# 10_HDMI.net
KiCad netlist of a schematic drawn in Altium Designer
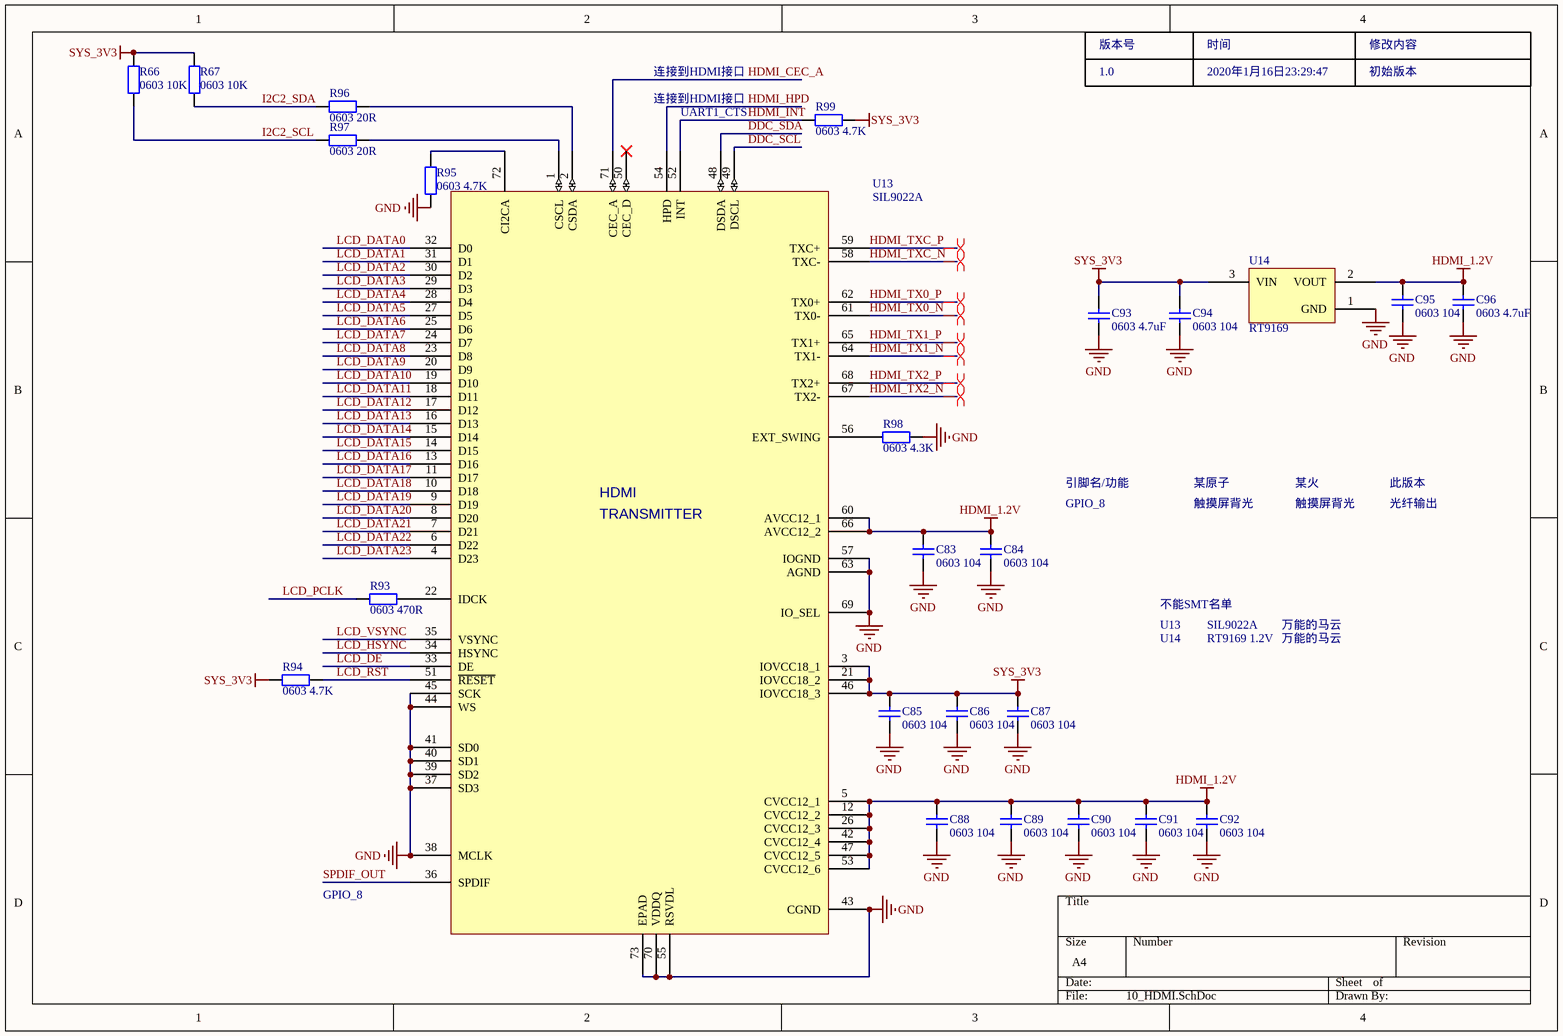
[diagram p0: 10_HDMI.SchDoc]

(export (version "E")
  (design (tool "Eeschema 10.0.6"))
  (components
    (comp (ref "C83")
      (value "0603 104")
      (footprint "LC-0603_C")
      (description "贴片电容")
      (libsource (lib "JLC") (part "0603 1.5nF (152) 10% 50V"))
    )
    (comp (ref "C84")
      (value "0603 104")
      (footprint "LC-0603_C")
      (description "贴片电容")
      (libsource (lib "JLC") (part "0603 1.5nF (152) 10% 50V"))
    )
    (comp (ref "C85")
      (value "0603 104")
      (footprint "LC-0603_C")
      (description "贴片电容")
      (libsource (lib "JLC") (part "0603 1.5nF (152) 10% 50V"))
    )
    (comp (ref "C86")
      (value "0603 104")
      (footprint "LC-0603_C")
      (description "贴片电容")
      (libsource (lib "JLC") (part "0603 1.5nF (152) 10% 50V"))
    )
    (comp (ref "C87")
      (value "0603 104")
      (footprint "LC-0603_C")
      (description "贴片电容")
      (libsource (lib "JLC") (part "0603 1.5nF (152) 10% 50V"))
    )
    (comp (ref "C88")
      (value "0603 104")
      (footprint "LC-0603_C")
      (description "贴片电容")
      (libsource (lib "JLC") (part "0603 1.5nF (152) 10% 50V"))
    )
    (comp (ref "C89")
      (value "0603 104")
      (footprint "LC-0603_C")
      (description "贴片电容")
      (libsource (lib "JLC") (part "0603 1.5nF (152) 10% 50V"))
    )
    (comp (ref "C90")
      (value "0603 104")
      (footprint "LC-0603_C")
      (description "贴片电容")
      (libsource (lib "JLC") (part "0603 1.5nF (152) 10% 50V"))
    )
    (comp (ref "C91")
      (value "0603 104")
      (footprint "LC-0603_C")
      (description "贴片电容")
      (libsource (lib "JLC") (part "0603 1.5nF (152) 10% 50V"))
    )
    (comp (ref "C92")
      (value "0603 104")
      (footprint "LC-0603_C")
      (description "贴片电容")
      (libsource (lib "JLC") (part "0603 1.5nF (152) 10% 50V"))
    )
    (comp (ref "C93")
      (value "0603 4.7uF")
      (footprint "LC-0603_C")
      (description "贴片电容")
      (libsource (lib "JLC") (part "0603 1.5nF (152) 10% 50V"))
    )
    (comp (ref "C94")
      (value "0603 104")
      (footprint "LC-0603_C")
      (description "贴片电容")
      (libsource (lib "JLC") (part "0603 1.5nF (152) 10% 50V"))
    )
    (comp (ref "C95")
      (value "0603 104")
      (footprint "LC-0603_C")
      (description "贴片电容")
      (libsource (lib "JLC") (part "0603 1.5nF (152) 10% 50V"))
    )
    (comp (ref "C96")
      (value "0603 4.7uF")
      (footprint "LC-0603_C")
      (description "贴片电容")
      (libsource (lib "JLC") (part "0603 1.5nF (152) 10% 50V"))
    )
    (comp (ref "R66")
      (value "0603 10K")
      (footprint "LC-0603_R")
      (description "贴片电阻")
      (libsource (lib "") (part "0603 1.1KΩ (1101) 1%_1"))
    )
    (comp (ref "R67")
      (value "0603 10K")
      (footprint "LC-0603_R")
      (description "贴片电阻")
      (libsource (lib "") (part "0603 1.1KΩ (1101) 1%_1"))
    )
    (comp (ref "R93")
      (value "0603 470R")
      (footprint "LC-0603_R")
      (description "贴片电阻")
      (libsource (lib "") (part "0603 1.1KΩ (1101) 1%_2"))
    )
    (comp (ref "R94")
      (value "0603 4.7K")
      (footprint "LC-0603_R")
      (description "贴片电阻")
      (libsource (lib "") (part "0603 1.1KΩ (1101) 1%_2"))
    )
    (comp (ref "R95")
      (value "0603 4.7K")
      (footprint "LC-0603_R")
      (description "贴片电阻")
      (libsource (lib "") (part "0603 1.1KΩ (1101) 1%_3"))
    )
    (comp (ref "R96")
      (value "0603 20R")
      (footprint "LC-0603_R")
      (description "贴片电阻")
      (libsource (lib "JLC") (part "0603 1.1KΩ (1101) 1%"))
    )
    (comp (ref "R97")
      (value "0603 20R")
      (footprint "LC-0603_R")
      (description "贴片电阻")
      (libsource (lib "JLC") (part "0603 1.1KΩ (1101) 1%"))
    )
    (comp (ref "R98")
      (value "0603 4.3K")
      (footprint "LC-0603_R")
      (description "贴片电阻")
      (libsource (lib "JLC") (part "0603 1.1KΩ (1101) 1%"))
    )
    (comp (ref "R99")
      (value "0603 4.7K")
      (footprint "LC-0603_R")
      (description "贴片电阻")
      (libsource (lib "JLC") (part "0603 1.1KΩ (1101) 1%"))
    )
    (comp (ref "U13")
      (value "SIL9022A")
      (footprint "QFN72_10X10")
      (libsource (lib "Integrated_Library2") (part "SIL9022A"))
    )
    (comp (ref "U14")
      (value "RT9169")
      (footprint "LC-SOT-23(SOT-23-3)")
      (libsource (lib "Integrated_Library2") (part "RT9169"))
    )
  )
  (nets
    (net (code "1") (name "/DDC_SCL") (class "Default")
      (node (ref "U13") (pin "49") (pinfunction "DSCL_49") (pintype "bidirectional"))
    )
    (net (code "2") (name "/DDC_SDA") (class "Default")
      (node (ref "U13") (pin "48") (pinfunction "DSDA_48") (pintype "bidirectional"))
    )
    (net (code "3") (name "/HDMI_CEC_A") (class "Default")
      (node (ref "U13") (pin "71") (pinfunction "CEC_A_71") (pintype "bidirectional"))
    )
    (net (code "4") (name "/HDMI_HPD") (class "Default")
      (node (ref "U13") (pin "54") (pinfunction "HPD_54") (pintype "passive"))
    )
    (net (code "5") (name "/HDMI_INT") (class "Default")
      (node (ref "R99") (pin "1") (pinfunction "1_1") (pintype "passive"))
      (node (ref "U13") (pin "52") (pinfunction "INT_52") (pintype "passive"))
    )
    (net (code "6") (name "/HDMI_TX0_N") (class "Default")
      (node (ref "U13") (pin "61") (pinfunction "TX0-_61") (pintype "passive"))
    )
    (net (code "7") (name "/HDMI_TX0_P") (class "Default")
      (node (ref "U13") (pin "62") (pinfunction "TX0+_62") (pintype "passive"))
    )
    (net (code "8") (name "/HDMI_TX1_N") (class "Default")
      (node (ref "U13") (pin "64") (pinfunction "TX1-_64") (pintype "passive"))
    )
    (net (code "9") (name "/HDMI_TX1_P") (class "Default")
      (node (ref "U13") (pin "65") (pinfunction "TX1+_65") (pintype "passive"))
    )
    (net (code "10") (name "/HDMI_TX2_N") (class "Default")
      (node (ref "U13") (pin "67") (pinfunction "TX2-_67") (pintype "passive"))
    )
    (net (code "11") (name "/HDMI_TX2_P") (class "Default")
      (node (ref "U13") (pin "68") (pinfunction "TX2+_68") (pintype "passive"))
    )
    (net (code "12") (name "/HDMI_TXC_N") (class "Default")
      (node (ref "U13") (pin "58") (pinfunction "TXC-_58") (pintype "passive"))
    )
    (net (code "13") (name "/HDMI_TXC_P") (class "Default")
      (node (ref "U13") (pin "59") (pinfunction "TXC+_59") (pintype "passive"))
    )
    (net (code "14") (name "/I2C2_SCL") (class "Default")
      (node (ref "R66") (pin "1") (pinfunction "1_1") (pintype "passive"))
      (node (ref "R97") (pin "1") (pinfunction "1_1") (pintype "passive"))
    )
    (net (code "15") (name "/I2C2_SDA") (class "Default")
      (node (ref "R67") (pin "1") (pinfunction "1_1") (pintype "passive"))
      (node (ref "R96") (pin "1") (pinfunction "1_1") (pintype "passive"))
    )
    (net (code "16") (name "/LCD_DATA0") (class "Default")
      (node (ref "U13") (pin "32") (pinfunction "D0_32") (pintype "passive"))
    )
    (net (code "17") (name "/LCD_DATA1") (class "Default")
      (node (ref "U13") (pin "31") (pinfunction "D1_31") (pintype "passive"))
    )
    (net (code "18") (name "/LCD_DATA2") (class "Default")
      (node (ref "U13") (pin "30") (pinfunction "D2_30") (pintype "passive"))
    )
    (net (code "19") (name "/LCD_DATA3") (class "Default")
      (node (ref "U13") (pin "29") (pinfunction "D3_29") (pintype "passive"))
    )
    (net (code "20") (name "/LCD_DATA4") (class "Default")
      (node (ref "U13") (pin "28") (pinfunction "D4_28") (pintype "passive"))
    )
    (net (code "21") (name "/LCD_DATA5") (class "Default")
      (node (ref "U13") (pin "27") (pinfunction "D5_27") (pintype "passive"))
    )
    (net (code "22") (name "/LCD_DATA6") (class "Default")
      (node (ref "U13") (pin "25") (pinfunction "D6_25") (pintype "passive"))
    )
    (net (code "23") (name "/LCD_DATA7") (class "Default")
      (node (ref "U13") (pin "24") (pinfunction "D7_24") (pintype "passive"))
    )
    (net (code "24") (name "/LCD_DATA8") (class "Default")
      (node (ref "U13") (pin "23") (pinfunction "D8_23") (pintype "passive"))
    )
    (net (code "25") (name "/LCD_DATA9") (class "Default")
      (node (ref "U13") (pin "20") (pinfunction "D9_20") (pintype "passive"))
    )
    (net (code "26") (name "/LCD_DATA10") (class "Default")
      (node (ref "U13") (pin "19") (pinfunction "D10_19") (pintype "passive"))
    )
    (net (code "27") (name "/LCD_DATA11") (class "Default")
      (node (ref "U13") (pin "18") (pinfunction "D11_18") (pintype "passive"))
    )
    (net (code "28") (name "/LCD_DATA12") (class "Default")
      (node (ref "U13") (pin "17") (pinfunction "D12_17") (pintype "passive"))
    )
    (net (code "29") (name "/LCD_DATA13") (class "Default")
      (node (ref "U13") (pin "16") (pinfunction "D13_16") (pintype "passive"))
    )
    (net (code "30") (name "/LCD_DATA14") (class "Default")
      (node (ref "U13") (pin "15") (pinfunction "D14_15") (pintype "passive"))
    )
    (net (code "31") (name "/LCD_DATA15") (class "Default")
      (node (ref "U13") (pin "14") (pinfunction "D15_14") (pintype "passive"))
    )
    (net (code "32") (name "/LCD_DATA16") (class "Default")
      (node (ref "U13") (pin "13") (pinfunction "D16_13") (pintype "passive"))
    )
    (net (code "33") (name "/LCD_DATA17") (class "Default")
      (node (ref "U13") (pin "11") (pinfunction "D17_11") (pintype "passive"))
    )
    (net (code "34") (name "/LCD_DATA18") (class "Default")
      (node (ref "U13") (pin "10") (pinfunction "D18_10") (pintype "passive"))
    )
    (net (code "35") (name "/LCD_DATA19") (class "Default")
      (node (ref "U13") (pin "9") (pinfunction "D19_9") (pintype "passive"))
    )
    (net (code "36") (name "/LCD_DATA20") (class "Default")
      (node (ref "U13") (pin "8") (pinfunction "D20_8") (pintype "passive"))
    )
    (net (code "37") (name "/LCD_DATA21") (class "Default")
      (node (ref "U13") (pin "7") (pinfunction "D21_7") (pintype "passive"))
    )
    (net (code "38") (name "/LCD_DATA22") (class "Default")
      (node (ref "U13") (pin "6") (pinfunction "D22_6") (pintype "passive"))
    )
    (net (code "39") (name "/LCD_DATA23") (class "Default")
      (node (ref "U13") (pin "4") (pinfunction "D23_4") (pintype "passive"))
    )
    (net (code "40") (name "/LCD_DE") (class "Default")
      (node (ref "U13") (pin "33") (pinfunction "DE_33") (pintype "passive"))
    )
    (net (code "41") (name "/LCD_HSYNC") (class "Default")
      (node (ref "U13") (pin "34") (pinfunction "HSYNC_34") (pintype "passive"))
    )
    (net (code "42") (name "/LCD_PCLK") (class "Default")
      (node (ref "R93") (pin "2") (pinfunction "2_2") (pintype "passive"))
    )
    (net (code "43") (name "/LCD_RST") (class "Default")
      (node (ref "R94") (pin "1") (pinfunction "1_1") (pintype "passive"))
      (node (ref "U13") (pin "51") (pinfunction "RESET_51") (pintype "passive"))
    )
    (net (code "44") (name "/LCD_VSYNC") (class "Default")
      (node (ref "U13") (pin "35") (pinfunction "VSYNC_35") (pintype "passive"))
    )
    (net (code "45") (name "/SPDIF_OUT") (class "Default")
      (node (ref "U13") (pin "36") (pinfunction "SPDIF_36") (pintype "passive"))
    )
    (net (code "46") (name "GND") (class "Default")
      (node (ref "C83") (pin "2") (pinfunction "2_2") (pintype "passive"))
      (node (ref "C84") (pin "2") (pinfunction "2_2") (pintype "passive"))
      (node (ref "C85") (pin "2") (pinfunction "2_2") (pintype "passive"))
      (node (ref "C86") (pin "2") (pinfunction "2_2") (pintype "passive"))
      (node (ref "C87") (pin "2") (pinfunction "2_2") (pintype "passive"))
      (node (ref "C88") (pin "2") (pinfunction "2_2") (pintype "passive"))
      (node (ref "C89") (pin "2") (pinfunction "2_2") (pintype "passive"))
      (node (ref "C90") (pin "2") (pinfunction "2_2") (pintype "passive"))
      (node (ref "C91") (pin "2") (pinfunction "2_2") (pintype "passive"))
      (node (ref "C92") (pin "2") (pinfunction "2_2") (pintype "passive"))
      (node (ref "C93") (pin "2") (pinfunction "2_2") (pintype "passive"))
      (node (ref "C94") (pin "2") (pinfunction "2_2") (pintype "passive"))
      (node (ref "C95") (pin "2") (pinfunction "2_2") (pintype "passive"))
      (node (ref "C96") (pin "2") (pinfunction "2_2") (pintype "passive"))
      (node (ref "R95") (pin "2") (pinfunction "2_2") (pintype "passive"))
      (node (ref "R98") (pin "2") (pinfunction "2_2") (pintype "passive"))
      (node (ref "U13") (pin "37") (pinfunction "SD3_37") (pintype "passive"))
      (node (ref "U13") (pin "38") (pinfunction "MCLK_38") (pintype "passive"))
      (node (ref "U13") (pin "39") (pinfunction "SD2_39") (pintype "passive"))
      (node (ref "U13") (pin "40") (pinfunction "SD1_40") (pintype "passive"))
      (node (ref "U13") (pin "41") (pinfunction "SD0_41") (pintype "passive"))
      (node (ref "U13") (pin "43") (pinfunction "CGND_43") (pintype "power_in"))
      (node (ref "U13") (pin "44") (pinfunction "WS_44") (pintype "passive"))
      (node (ref "U13") (pin "45") (pinfunction "SCK_45") (pintype "passive"))
      (node (ref "U13") (pin "55") (pinfunction "RSVDL_55") (pintype "passive"))
      (node (ref "U13") (pin "57") (pinfunction "IOGND_57") (pintype "power_in"))
      (node (ref "U13") (pin "63") (pinfunction "AGND_63") (pintype "power_in"))
      (node (ref "U13") (pin "69") (pinfunction "IO_SEL_69") (pintype "passive"))
      (node (ref "U13") (pin "70") (pinfunction "VDDQ_70") (pintype "power_in"))
      (node (ref "U13") (pin "73") (pinfunction "EPAD_73") (pintype "power_in"))
      (node (ref "U14") (pin "1") (pinfunction "GND_1") (pintype "passive"))
    )
    (net (code "47") (name "HDMI_1.2V") (class "Default")
      (node (ref "C83") (pin "1") (pinfunction "1_1") (pintype "passive"))
      (node (ref "C84") (pin "1") (pinfunction "1_1") (pintype "passive"))
      (node (ref "C88") (pin "1") (pinfunction "1_1") (pintype "passive"))
      (node (ref "C89") (pin "1") (pinfunction "1_1") (pintype "passive"))
      (node (ref "C90") (pin "1") (pinfunction "1_1") (pintype "passive"))
      (node (ref "C91") (pin "1") (pinfunction "1_1") (pintype "passive"))
      (node (ref "C92") (pin "1") (pinfunction "1_1") (pintype "passive"))
      (node (ref "C95") (pin "1") (pinfunction "1_1") (pintype "passive"))
      (node (ref "C96") (pin "1") (pinfunction "1_1") (pintype "passive"))
      (node (ref "U13") (pin "12") (pinfunction "CVCC12_2_12") (pintype "power_in"))
      (node (ref "U13") (pin "26") (pinfunction "CVCC12_3_26") (pintype "power_in"))
      (node (ref "U13") (pin "42") (pinfunction "CVCC12_4_42") (pintype "power_in"))
      (node (ref "U13") (pin "47") (pinfunction "CVCC12_5_47") (pintype "power_in"))
      (node (ref "U13") (pin "5") (pinfunction "CVCC12_1_5") (pintype "power_in"))
      (node (ref "U13") (pin "53") (pinfunction "CVCC12_6_53") (pintype "power_in"))
      (node (ref "U13") (pin "60") (pinfunction "AVCC12_1_60") (pintype "power_in"))
      (node (ref "U13") (pin "66") (pinfunction "AVCC12_2_66") (pintype "power_in"))
      (node (ref "U14") (pin "2") (pinfunction "VOUT_2") (pintype "passive"))
    )
    (net (code "48") (name "Net-(U13-CI2CA)") (class "Default")
      (node (ref "R95") (pin "1") (pinfunction "1_1") (pintype "passive"))
      (node (ref "U13") (pin "72") (pinfunction "CI2CA_72") (pintype "passive"))
    )
    (net (code "49") (name "Net-(U13-CSCL)") (class "Default")
      (node (ref "R97") (pin "2") (pinfunction "2_2") (pintype "passive"))
      (node (ref "U13") (pin "1") (pinfunction "CSCL_1") (pintype "bidirectional"))
    )
    (net (code "50") (name "Net-(U13-CSDA)") (class "Default")
      (node (ref "R96") (pin "2") (pinfunction "2_2") (pintype "passive"))
      (node (ref "U13") (pin "2") (pinfunction "CSDA_2") (pintype "bidirectional"))
    )
    (net (code "51") (name "Net-(U13-EXT_SWING)") (class "Default")
      (node (ref "R98") (pin "1") (pinfunction "1_1") (pintype "passive"))
      (node (ref "U13") (pin "56") (pinfunction "EXT_SWING_56") (pintype "passive"))
    )
    (net (code "52") (name "Net-(U13-IDCK)") (class "Default")
      (node (ref "R93") (pin "1") (pinfunction "1_1") (pintype "passive"))
      (node (ref "U13") (pin "22") (pinfunction "IDCK_22") (pintype "passive"))
    )
    (net (code "53") (name "SYS_3V3") (class "Default")
      (node (ref "C85") (pin "1") (pinfunction "1_1") (pintype "passive"))
      (node (ref "C86") (pin "1") (pinfunction "1_1") (pintype "passive"))
      (node (ref "C87") (pin "1") (pinfunction "1_1") (pintype "passive"))
      (node (ref "C93") (pin "1") (pinfunction "1_1") (pintype "passive"))
      (node (ref "C94") (pin "1") (pinfunction "1_1") (pintype "passive"))
      (node (ref "R66") (pin "2") (pinfunction "2_2") (pintype "passive"))
      (node (ref "R67") (pin "2") (pinfunction "2_2") (pintype "passive"))
      (node (ref "R94") (pin "2") (pinfunction "2_2") (pintype "passive"))
      (node (ref "R99") (pin "2") (pinfunction "2_2") (pintype "passive"))
      (node (ref "U13") (pin "21") (pinfunction "IOVCC18_2_21") (pintype "power_in"))
      (node (ref "U13") (pin "3") (pinfunction "IOVCC18_1_3") (pintype "power_in"))
      (node (ref "U13") (pin "46") (pinfunction "IOVCC18_3_46") (pintype "power_in"))
      (node (ref "U14") (pin "3") (pinfunction "VIN_3") (pintype "passive"))
    )
    (net (code "54") (name "unconnected-(U13-CEC_D-Pad50)") (class "Default")
      (node (ref "U13") (pin "50") (pinfunction "CEC_D_50") (pintype "bidirectional+no_connect"))
    )
  )
)
